# button_io.net
KiCad netlist of a schematic drawn in Altium Designer
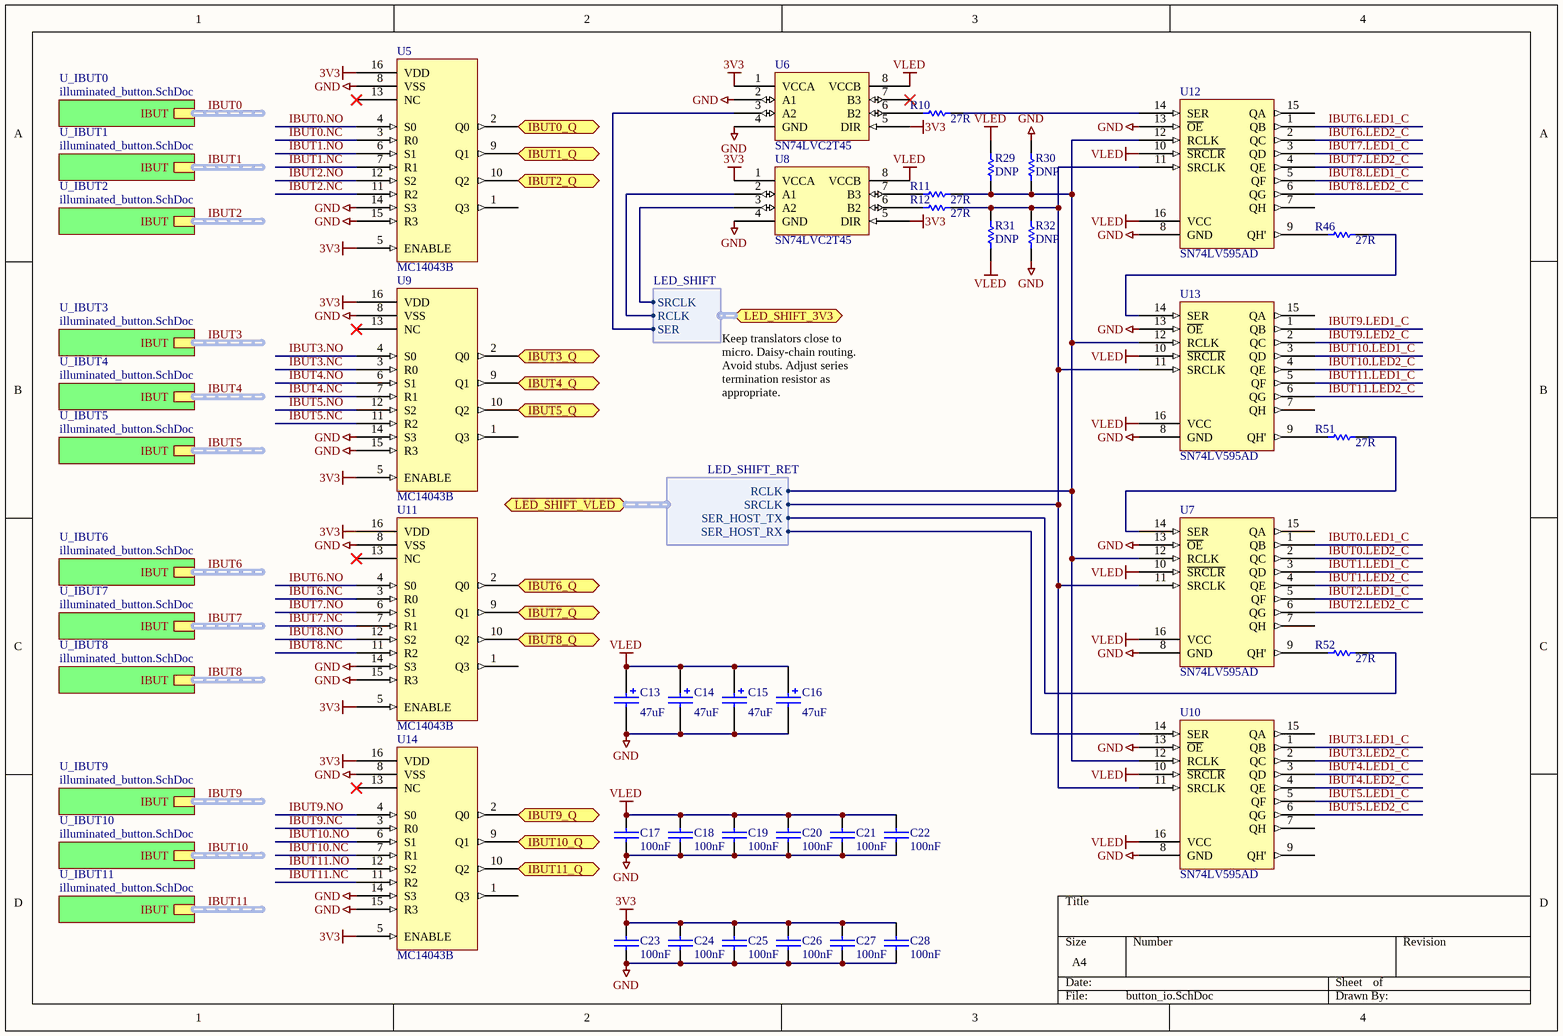
[diagram p0: button_io.SchDoc]

(export (version "E")
  (design (tool "Eeschema 10.0.6"))
  (components
    (comp (ref "C13")
      (value "47uF")
      (footprint "CAPMP7343X19N (Murata D4)")
      (description "Polarized Capacitor (Surface Mount)")
      (fields
        (field (name "MANUFACTURER") "Generic Components")
        (field (name "MANUFACTURER PART NUMBER") "ECASD40J476M025K00")
        (field (name "PUBLISHER") "Altium Limited")
      )
      (libsource (lib "RCLDQ") (part "CAP POL3"))
    )
    (comp (ref "C14")
      (value "47uF")
      (footprint "CAPMP7343X19N (Murata D4)")
      (description "Polarized Capacitor (Surface Mount)")
      (fields
        (field (name "MANUFACTURER") "Generic Components")
        (field (name "MANUFACTURER PART NUMBER") "ECASD40J476M025K00")
        (field (name "PUBLISHER") "Altium Limited")
      )
      (libsource (lib "RCLDQ") (part "CAP POL3"))
    )
    (comp (ref "C15")
      (value "47uF")
      (footprint "CAPMP7343X19N (Murata D4)")
      (description "Polarized Capacitor (Surface Mount)")
      (fields
        (field (name "MANUFACTURER") "Generic Components")
        (field (name "MANUFACTURER PART NUMBER") "ECASD40J476M025K00")
        (field (name "PUBLISHER") "Altium Limited")
      )
      (libsource (lib "RCLDQ") (part "CAP POL3"))
    )
    (comp (ref "C16")
      (value "47uF")
      (footprint "CAPMP7343X19N (Murata D4)")
      (description "Polarized Capacitor (Surface Mount)")
      (fields
        (field (name "MANUFACTURER") "Generic Components")
        (field (name "MANUFACTURER PART NUMBER") "ECASD40J476M025K00")
        (field (name "PUBLISHER") "Altium Limited")
      )
      (libsource (lib "RCLDQ") (part "CAP POL3"))
    )
    (comp (ref "C17")
      (value "100nF")
      (footprint "0603")
      (description "Capacitor")
      (fields
        (field (name "MANUFACTURER") "TDK Corporation")
        (field (name "MANUFACTURER PART NUMBER") "C1608X7R1H103K080AA")
      )
      (libsource (lib "*") (part "CAP"))
    )
    (comp (ref "C18")
      (value "100nF")
      (footprint "0603")
      (description "Capacitor")
      (fields
        (field (name "MANUFACTURER") "TDK Corporation")
        (field (name "MANUFACTURER PART NUMBER") "C1608X7R1H103K080AA")
      )
      (libsource (lib "*") (part "CAP"))
    )
    (comp (ref "C19")
      (value "100nF")
      (footprint "0603")
      (description "Capacitor")
      (fields
        (field (name "MANUFACTURER") "TDK Corporation")
        (field (name "MANUFACTURER PART NUMBER") "C1608X7R1H103K080AA")
      )
      (libsource (lib "*") (part "CAP"))
    )
    (comp (ref "C20")
      (value "100nF")
      (footprint "0603")
      (description "Capacitor")
      (fields
        (field (name "MANUFACTURER") "TDK Corporation")
        (field (name "MANUFACTURER PART NUMBER") "C1608X7R1H103K080AA")
      )
      (libsource (lib "*") (part "CAP"))
    )
    (comp (ref "C21")
      (value "100nF")
      (footprint "0603")
      (description "Capacitor")
      (fields
        (field (name "MANUFACTURER") "TDK Corporation")
        (field (name "MANUFACTURER PART NUMBER") "C1608X7R1H103K080AA")
      )
      (libsource (lib "*") (part "CAP"))
    )
    (comp (ref "C22")
      (value "100nF")
      (footprint "0603")
      (description "Capacitor")
      (fields
        (field (name "MANUFACTURER") "TDK Corporation")
        (field (name "MANUFACTURER PART NUMBER") "C1608X7R1H103K080AA")
      )
      (libsource (lib "*") (part "CAP"))
    )
    (comp (ref "C23")
      (value "100nF")
      (footprint "0603")
      (description "Capacitor")
      (fields
        (field (name "MANUFACTURER") "TDK Corporation")
        (field (name "MANUFACTURER PART NUMBER") "C1608X7R1H103K080AA")
      )
      (libsource (lib "*") (part "CAP"))
    )
    (comp (ref "C24")
      (value "100nF")
      (footprint "0603")
      (description "Capacitor")
      (fields
        (field (name "MANUFACTURER") "TDK Corporation")
        (field (name "MANUFACTURER PART NUMBER") "C1608X7R1H103K080AA")
      )
      (libsource (lib "*") (part "CAP"))
    )
    (comp (ref "C25")
      (value "100nF")
      (footprint "0603")
      (description "Capacitor")
      (fields
        (field (name "MANUFACTURER") "TDK Corporation")
        (field (name "MANUFACTURER PART NUMBER") "C1608X7R1H103K080AA")
      )
      (libsource (lib "*") (part "CAP"))
    )
    (comp (ref "C26")
      (value "100nF")
      (footprint "0603")
      (description "Capacitor")
      (fields
        (field (name "MANUFACTURER") "TDK Corporation")
        (field (name "MANUFACTURER PART NUMBER") "C1608X7R1H103K080AA")
      )
      (libsource (lib "*") (part "CAP"))
    )
    (comp (ref "C27")
      (value "100nF")
      (footprint "0603")
      (description "Capacitor")
      (fields
        (field (name "MANUFACTURER") "TDK Corporation")
        (field (name "MANUFACTURER PART NUMBER") "C1608X7R1H103K080AA")
      )
      (libsource (lib "*") (part "CAP"))
    )
    (comp (ref "C28")
      (value "100nF")
      (footprint "0603")
      (description "Capacitor")
      (fields
        (field (name "MANUFACTURER") "TDK Corporation")
        (field (name "MANUFACTURER PART NUMBER") "C1608X7R1H103K080AA")
      )
      (libsource (lib "*") (part "CAP"))
    )
    (comp (ref "R10")
      (value "27R")
      (footprint "0603")
      (description "Semiconductor Resistor")
      (fields
        (field (name "MANUFACTURER") "Panasonic Electronic Components")
        (field (name "MANUFACTURER PART NUMBER") "ERJ-3EKF27R0V")
        (field (name "PUBLISHER") "Altium Limited")
      )
      (libsource (lib "Miscellaneous Devices") (part "Res Semi"))
    )
    (comp (ref "R11")
      (value "27R")
      (footprint "0603")
      (description "Semiconductor Resistor")
      (fields
        (field (name "MANUFACTURER") "Panasonic Electronic Components")
        (field (name "MANUFACTURER PART NUMBER") "ERJ-3EKF27R0V")
        (field (name "PUBLISHER") "Altium Limited")
      )
      (libsource (lib "Miscellaneous Devices") (part "Res Semi"))
    )
    (comp (ref "R12")
      (value "27R")
      (footprint "0603")
      (description "Semiconductor Resistor")
      (fields
        (field (name "MANUFACTURER") "Panasonic Electronic Components")
        (field (name "MANUFACTURER PART NUMBER") "ERJ-3EKF27R0V")
        (field (name "PUBLISHER") "Altium Limited")
      )
      (libsource (lib "Miscellaneous Devices") (part "Res Semi"))
    )
    (comp (ref "R29")
      (value "DNP")
      (footprint "0603")
      (description "Semiconductor Resistor")
      (fields (field (name "PUBLISHER") "Altium Limited"))
      (libsource (lib "Miscellaneous Devices") (part "Res Semi"))
    )
    (comp (ref "R30")
      (value "DNP")
      (footprint "0603")
      (description "Semiconductor Resistor")
      (fields (field (name "PUBLISHER") "Altium Limited"))
      (libsource (lib "Miscellaneous Devices") (part "Res Semi"))
    )
    (comp (ref "R31")
      (value "DNP")
      (footprint "0603")
      (description "Semiconductor Resistor")
      (fields (field (name "PUBLISHER") "Altium Limited"))
      (libsource (lib "Miscellaneous Devices") (part "Res Semi"))
    )
    (comp (ref "R32")
      (value "DNP")
      (footprint "0603")
      (description "Semiconductor Resistor")
      (fields (field (name "PUBLISHER") "Altium Limited"))
      (libsource (lib "Miscellaneous Devices") (part "Res Semi"))
    )
    (comp (ref "R46")
      (value "27R")
      (footprint "0603")
      (description "Semiconductor Resistor")
      (fields
        (field (name "MANUFACTURER") "Panasonic Electronic Components")
        (field (name "MANUFACTURER PART NUMBER") "ERJ-3EKF27R0V")
        (field (name "PUBLISHER") "Altium Limited")
      )
      (libsource (lib "Miscellaneous Devices") (part "Res Semi"))
    )
    (comp (ref "R51")
      (value "27R")
      (footprint "0603")
      (description "Semiconductor Resistor")
      (fields
        (field (name "MANUFACTURER") "Panasonic Electronic Components")
        (field (name "MANUFACTURER PART NUMBER") "ERJ-3EKF27R0V")
        (field (name "PUBLISHER") "Altium Limited")
      )
      (libsource (lib "Miscellaneous Devices") (part "Res Semi"))
    )
    (comp (ref "R52")
      (value "27R")
      (footprint "0603")
      (description "Semiconductor Resistor")
      (fields
        (field (name "MANUFACTURER") "Panasonic Electronic Components")
        (field (name "MANUFACTURER PART NUMBER") "ERJ-3EKF27R0V")
        (field (name "PUBLISHER") "Altium Limited")
      )
      (libsource (lib "Miscellaneous Devices") (part "Res Semi"))
    )
    (comp (ref "U5")
      (value "MC14043B")
      (footprint "SOIC127P600X175-16N")
      (description "Quad CMOS R-S Latches")
      (fields (field (name "PART NUMBER") "MC14043BDR2G") (field (name "MANUFACTURER") "ON Semiconductor"))
      (libsource (lib "steve") (part "MC14043B"))
    )
    (comp (ref "U6")
      (value "SN74LVC2T45")
      (footprint "TSOP65P400X130-8N")
      (description "Dual-bit  Dual-supply Bus Transceiver")
      (fields (field (name "PART NUMBER") "SN74LVC2T45DCT") (field (name "MANUFACTURER") "Texas Instruments"))
      (libsource (lib "steve") (part "SN74LVC2T45"))
    )
    (comp (ref "U7")
      (value "SN74LV595AD")
      (footprint "SOIC127P600X175-16N")
      (description "8-Bit Shift Registers with 3-State Output Registers")
      (fields
        (field (name "MANUFACTURER") "Texas Instruments")
        (field (name "MANUFACTURER PART NUMBER") "SN74LV595ADR")
      )
      (libsource (lib "steve") (part "SN74LV595AD"))
    )
    (comp (ref "U8")
      (value "SN74LVC2T45")
      (footprint "TSOP65P400X130-8N")
      (description "Dual-bit  Dual-supply Bus Transceiver")
      (fields (field (name "PART NUMBER") "SN74LVC2T45DCT") (field (name "MANUFACTURER") "Texas Instruments"))
      (libsource (lib "steve") (part "SN74LVC2T45"))
    )
    (comp (ref "U9")
      (value "MC14043B")
      (footprint "SOIC127P600X175-16N")
      (description "Quad CMOS R-S Latches")
      (fields (field (name "PART NUMBER") "MC14043BDR2G") (field (name "MANUFACTURER") "ON Semiconductor"))
      (libsource (lib "steve") (part "MC14043B"))
    )
    (comp (ref "U10")
      (value "SN74LV595AD")
      (footprint "SOIC127P600X175-16N")
      (description "8-Bit Shift Registers with 3-State Output Registers")
      (fields
        (field (name "MANUFACTURER") "Texas Instruments")
        (field (name "MANUFACTURER PART NUMBER") "SN74LV595ADR")
      )
      (libsource (lib "steve") (part "SN74LV595AD"))
    )
    (comp (ref "U11")
      (value "MC14043B")
      (footprint "SOIC127P600X175-16N")
      (description "Quad CMOS R-S Latches")
      (fields (field (name "PART NUMBER") "MC14043BDR2G") (field (name "MANUFACTURER") "ON Semiconductor"))
      (libsource (lib "steve") (part "MC14043B"))
    )
    (comp (ref "U12")
      (value "SN74LV595AD")
      (footprint "SOIC127P600X175-16N")
      (description "8-Bit Shift Registers with 3-State Output Registers")
      (fields
        (field (name "MANUFACTURER") "Texas Instruments")
        (field (name "MANUFACTURER PART NUMBER") "SN74LV595ADR")
      )
      (libsource (lib "steve") (part "SN74LV595AD"))
    )
    (comp (ref "U13")
      (value "SN74LV595AD")
      (footprint "SOIC127P600X175-16N")
      (description "8-Bit Shift Registers with 3-State Output Registers")
      (fields
        (field (name "MANUFACTURER") "Texas Instruments")
        (field (name "MANUFACTURER PART NUMBER") "SN74LV595ADR")
      )
      (libsource (lib "steve") (part "SN74LV595AD"))
    )
    (comp (ref "U14")
      (value "MC14043B")
      (footprint "SOIC127P600X175-16N")
      (description "Quad CMOS R-S Latches")
      (fields (field (name "PART NUMBER") "MC14043BDR2G") (field (name "MANUFACTURER") "ON Semiconductor"))
      (libsource (lib "steve") (part "MC14043B"))
    )
  )
  (nets
    (net (code "15") (name "/IBUT0.LED1_C") (class "Default")
      (node (ref "U7") (pin "1") (pinfunction "QB_1") (pintype "output"))
    )
    (net (code "16") (name "/IBUT0.LED2_C") (class "Default")
      (node (ref "U7") (pin "2") (pinfunction "QC_2") (pintype "output"))
    )
    (net (code "17") (name "/IBUT0.NC") (class "Default")
      (node (ref "U5") (pin "3") (pinfunction "R0_3") (pintype "input"))
    )
    (net (code "18") (name "/IBUT0.NO") (class "Default")
      (node (ref "U5") (pin "4") (pinfunction "S0_4") (pintype "input"))
    )
    (net (code "19") (name "/IBUT0_Q") (class "Default")
      (node (ref "U5") (pin "2") (pinfunction "Q0_2") (pintype "output"))
    )
    (net (code "20") (name "/IBUT1.LED1_C") (class "Default")
      (node (ref "U7") (pin "3") (pinfunction "QD_3") (pintype "output"))
    )
    (net (code "21") (name "/IBUT1.LED2_C") (class "Default")
      (node (ref "U7") (pin "4") (pinfunction "QE_4") (pintype "output"))
    )
    (net (code "22") (name "/IBUT1.NC") (class "Default")
      (node (ref "U5") (pin "7") (pinfunction "R1_7") (pintype "input"))
    )
    (net (code "23") (name "/IBUT1.NO") (class "Default")
      (node (ref "U5") (pin "6") (pinfunction "S1_6") (pintype "input"))
    )
    (net (code "24") (name "/IBUT1_Q") (class "Default")
      (node (ref "U5") (pin "9") (pinfunction "Q1_9") (pintype "output"))
    )
    (net (code "25") (name "/IBUT2.LED1_C") (class "Default")
      (node (ref "U7") (pin "5") (pinfunction "QF_5") (pintype "output"))
    )
    (net (code "26") (name "/IBUT2.LED2_C") (class "Default")
      (node (ref "U7") (pin "6") (pinfunction "QG_6") (pintype "output"))
    )
    (net (code "27") (name "/IBUT2.NC") (class "Default")
      (node (ref "U5") (pin "11") (pinfunction "R2_11") (pintype "input"))
    )
    (net (code "28") (name "/IBUT2.NO") (class "Default")
      (node (ref "U5") (pin "12") (pinfunction "S2_12") (pintype "input"))
    )
    (net (code "29") (name "/IBUT2_Q") (class "Default")
      (node (ref "U5") (pin "10") (pinfunction "Q2_10") (pintype "output"))
    )
    (net (code "30") (name "/IBUT3.LED1_C") (class "Default")
      (node (ref "U10") (pin "1") (pinfunction "QB_1") (pintype "output"))
    )
    (net (code "31") (name "/IBUT3.LED2_C") (class "Default")
      (node (ref "U10") (pin "2") (pinfunction "QC_2") (pintype "output"))
    )
    (net (code "32") (name "/IBUT3.NC") (class "Default")
      (node (ref "U9") (pin "3") (pinfunction "R0_3") (pintype "input"))
    )
    (net (code "33") (name "/IBUT3.NO") (class "Default")
      (node (ref "U9") (pin "4") (pinfunction "S0_4") (pintype "input"))
    )
    (net (code "34") (name "/IBUT3_Q") (class "Default")
      (node (ref "U9") (pin "2") (pinfunction "Q0_2") (pintype "output"))
    )
    (net (code "35") (name "/IBUT4.LED1_C") (class "Default")
      (node (ref "U10") (pin "3") (pinfunction "QD_3") (pintype "output"))
    )
    (net (code "36") (name "/IBUT4.LED2_C") (class "Default")
      (node (ref "U10") (pin "4") (pinfunction "QE_4") (pintype "output"))
    )
    (net (code "37") (name "/IBUT4.NC") (class "Default")
      (node (ref "U9") (pin "7") (pinfunction "R1_7") (pintype "input"))
    )
    (net (code "38") (name "/IBUT4.NO") (class "Default")
      (node (ref "U9") (pin "6") (pinfunction "S1_6") (pintype "input"))
    )
    (net (code "39") (name "/IBUT4_Q") (class "Default")
      (node (ref "U9") (pin "9") (pinfunction "Q1_9") (pintype "output"))
    )
    (net (code "40") (name "/IBUT5.LED1_C") (class "Default")
      (node (ref "U10") (pin "5") (pinfunction "QF_5") (pintype "output"))
    )
    (net (code "41") (name "/IBUT5.LED2_C") (class "Default")
      (node (ref "U10") (pin "6") (pinfunction "QG_6") (pintype "output"))
    )
    (net (code "42") (name "/IBUT5.NC") (class "Default")
      (node (ref "U9") (pin "11") (pinfunction "R2_11") (pintype "input"))
    )
    (net (code "43") (name "/IBUT5.NO") (class "Default")
      (node (ref "U9") (pin "12") (pinfunction "S2_12") (pintype "input"))
    )
    (net (code "44") (name "/IBUT5_Q") (class "Default")
      (node (ref "U9") (pin "10") (pinfunction "Q2_10") (pintype "output"))
    )
    (net (code "45") (name "/IBUT6.LED1_C") (class "Default")
      (node (ref "U12") (pin "1") (pinfunction "QB_1") (pintype "output"))
    )
    (net (code "46") (name "/IBUT6.LED2_C") (class "Default")
      (node (ref "U12") (pin "2") (pinfunction "QC_2") (pintype "output"))
    )
    (net (code "47") (name "/IBUT6.NC") (class "Default")
      (node (ref "U11") (pin "3") (pinfunction "R0_3") (pintype "input"))
    )
    (net (code "48") (name "/IBUT6.NO") (class "Default")
      (node (ref "U11") (pin "4") (pinfunction "S0_4") (pintype "input"))
    )
    (net (code "49") (name "/IBUT6_Q") (class "Default")
      (node (ref "U11") (pin "2") (pinfunction "Q0_2") (pintype "output"))
    )
    (net (code "50") (name "/IBUT7.LED1_C") (class "Default")
      (node (ref "U12") (pin "3") (pinfunction "QD_3") (pintype "output"))
    )
    (net (code "51") (name "/IBUT7.LED2_C") (class "Default")
      (node (ref "U12") (pin "4") (pinfunction "QE_4") (pintype "output"))
    )
    (net (code "52") (name "/IBUT7.NC") (class "Default")
      (node (ref "U11") (pin "7") (pinfunction "R1_7") (pintype "input"))
    )
    (net (code "53") (name "/IBUT7.NO") (class "Default")
      (node (ref "U11") (pin "6") (pinfunction "S1_6") (pintype "input"))
    )
    (net (code "54") (name "/IBUT7_Q") (class "Default")
      (node (ref "U11") (pin "9") (pinfunction "Q1_9") (pintype "output"))
    )
    (net (code "55") (name "/IBUT8.LED1_C") (class "Default")
      (node (ref "U12") (pin "5") (pinfunction "QF_5") (pintype "output"))
    )
    (net (code "56") (name "/IBUT8.LED2_C") (class "Default")
      (node (ref "U12") (pin "6") (pinfunction "QG_6") (pintype "output"))
    )
    (net (code "57") (name "/IBUT8.NC") (class "Default")
      (node (ref "U11") (pin "11") (pinfunction "R2_11") (pintype "input"))
    )
    (net (code "58") (name "/IBUT8.NO") (class "Default")
      (node (ref "U11") (pin "12") (pinfunction "S2_12") (pintype "input"))
    )
    (net (code "59") (name "/IBUT8_Q") (class "Default")
      (node (ref "U11") (pin "10") (pinfunction "Q2_10") (pintype "output"))
    )
    (net (code "60") (name "/IBUT9.LED1_C") (class "Default")
      (node (ref "U13") (pin "1") (pinfunction "QB_1") (pintype "output"))
    )
    (net (code "61") (name "/IBUT9.LED2_C") (class "Default")
      (node (ref "U13") (pin "2") (pinfunction "QC_2") (pintype "output"))
    )
    (net (code "62") (name "/IBUT9.NC") (class "Default")
      (node (ref "U14") (pin "3") (pinfunction "R0_3") (pintype "input"))
    )
    (net (code "63") (name "/IBUT9.NO") (class "Default")
      (node (ref "U14") (pin "4") (pinfunction "S0_4") (pintype "input"))
    )
    (net (code "64") (name "/IBUT9_Q") (class "Default")
      (node (ref "U14") (pin "2") (pinfunction "Q0_2") (pintype "output"))
    )
    (net (code "65") (name "/IBUT10.LED1_C") (class "Default")
      (node (ref "U13") (pin "3") (pinfunction "QD_3") (pintype "output"))
    )
    (net (code "66") (name "/IBUT10.LED2_C") (class "Default")
      (node (ref "U13") (pin "4") (pinfunction "QE_4") (pintype "output"))
    )
    (net (code "67") (name "/IBUT10.NC") (class "Default")
      (node (ref "U14") (pin "7") (pinfunction "R1_7") (pintype "input"))
    )
    (net (code "68") (name "/IBUT10.NO") (class "Default")
      (node (ref "U14") (pin "6") (pinfunction "S1_6") (pintype "input"))
    )
    (net (code "69") (name "/IBUT10_Q") (class "Default")
      (node (ref "U14") (pin "9") (pinfunction "Q1_9") (pintype "output"))
    )
    (net (code "70") (name "/IBUT11.LED1_C") (class "Default")
      (node (ref "U13") (pin "5") (pinfunction "QF_5") (pintype "output"))
    )
    (net (code "71") (name "/IBUT11.LED2_C") (class "Default")
      (node (ref "U13") (pin "6") (pinfunction "QG_6") (pintype "output"))
    )
    (net (code "72") (name "/IBUT11.NC") (class "Default")
      (node (ref "U14") (pin "11") (pinfunction "R2_11") (pintype "input"))
    )
    (net (code "73") (name "/IBUT11.NO") (class "Default")
      (node (ref "U14") (pin "12") (pinfunction "S2_12") (pintype "input"))
    )
    (net (code "74") (name "/IBUT11_Q") (class "Default")
      (node (ref "U14") (pin "10") (pinfunction "Q2_10") (pintype "output"))
    )
    (net (code "75") (name "/SER") (class "Default")
      (node (ref "U6") (pin "3") (pinfunction "A2_3") (pintype "bidirectional"))
    )
    (net (code "76") (name "/SER_HOST_RX") (class "Default")
      (node (ref "U10") (pin "14") (pinfunction "SER_14") (pintype "input"))
    )
    (net (code "77") (name "/SER_HOST_TX") (class "Default")
      (node (ref "R52") (pin "1") (pinfunction "1_1") (pintype "passive"))
    )
    (net (code "92") (name "3V3") (class "Default")
      (node (ref "C23") (pin "1") (pinfunction "1_1") (pintype "passive"))
      (node (ref "C24") (pin "1") (pinfunction "1_1") (pintype "passive"))
      (node (ref "C25") (pin "1") (pinfunction "1_1") (pintype "passive"))
      (node (ref "C26") (pin "1") (pinfunction "1_1") (pintype "passive"))
      (node (ref "C27") (pin "1") (pinfunction "1_1") (pintype "passive"))
      (node (ref "C28") (pin "1") (pinfunction "1_1") (pintype "passive"))
      (node (ref "U11") (pin "16") (pinfunction "VDD_16") (pintype "power_in"))
      (node (ref "U11") (pin "5") (pinfunction "ENABLE_5") (pintype "input"))
      (node (ref "U14") (pin "16") (pinfunction "VDD_16") (pintype "power_in"))
      (node (ref "U14") (pin "5") (pinfunction "ENABLE_5") (pintype "input"))
      (node (ref "U5") (pin "16") (pinfunction "VDD_16") (pintype "power_in"))
      (node (ref "U5") (pin "5") (pinfunction "ENABLE_5") (pintype "input"))
      (node (ref "U6") (pin "1") (pinfunction "VCCA_1") (pintype "power_in"))
      (node (ref "U6") (pin "5") (pinfunction "DIR_5") (pintype "input"))
      (node (ref "U8") (pin "1") (pinfunction "VCCA_1") (pintype "power_in"))
      (node (ref "U8") (pin "5") (pinfunction "DIR_5") (pintype "input"))
      (node (ref "U9") (pin "16") (pinfunction "VDD_16") (pintype "power_in"))
      (node (ref "U9") (pin "5") (pinfunction "ENABLE_5") (pintype "input"))
    )
    (net (code "93") (name "GND") (class "Default")
      (node (ref "C13") (pin "2") (pinfunction "2_2") (pintype "passive"))
      (node (ref "C14") (pin "2") (pinfunction "2_2") (pintype "passive"))
      (node (ref "C15") (pin "2") (pinfunction "2_2") (pintype "passive"))
      (node (ref "C16") (pin "2") (pinfunction "2_2") (pintype "passive"))
      (node (ref "C17") (pin "2") (pinfunction "2_2") (pintype "passive"))
      (node (ref "C18") (pin "2") (pinfunction "2_2") (pintype "passive"))
      (node (ref "C19") (pin "2") (pinfunction "2_2") (pintype "passive"))
      (node (ref "C20") (pin "2") (pinfunction "2_2") (pintype "passive"))
      (node (ref "C21") (pin "2") (pinfunction "2_2") (pintype "passive"))
      (node (ref "C22") (pin "2") (pinfunction "2_2") (pintype "passive"))
      (node (ref "C23") (pin "2") (pinfunction "2_2") (pintype "passive"))
      (node (ref "C24") (pin "2") (pinfunction "2_2") (pintype "passive"))
      (node (ref "C25") (pin "2") (pinfunction "2_2") (pintype "passive"))
      (node (ref "C26") (pin "2") (pinfunction "2_2") (pintype "passive"))
      (node (ref "C27") (pin "2") (pinfunction "2_2") (pintype "passive"))
      (node (ref "C28") (pin "2") (pinfunction "2_2") (pintype "passive"))
      (node (ref "R30") (pin "1") (pinfunction "1_1") (pintype "passive"))
      (node (ref "R32") (pin "2") (pinfunction "2_2") (pintype "passive"))
      (node (ref "U10") (pin "13") (pinfunction "~{OE}_13") (pintype "input"))
      (node (ref "U10") (pin "8") (pinfunction "GND_8") (pintype "power_in"))
      (node (ref "U11") (pin "14") (pinfunction "S3_14") (pintype "input"))
      (node (ref "U11") (pin "15") (pinfunction "R3_15") (pintype "input"))
      (node (ref "U11") (pin "8") (pinfunction "VSS_8") (pintype "power_in"))
      (node (ref "U12") (pin "13") (pinfunction "~{OE}_13") (pintype "input"))
      (node (ref "U12") (pin "8") (pinfunction "GND_8") (pintype "power_in"))
      (node (ref "U13") (pin "13") (pinfunction "~{OE}_13") (pintype "input"))
      (node (ref "U13") (pin "8") (pinfunction "GND_8") (pintype "power_in"))
      (node (ref "U14") (pin "14") (pinfunction "S3_14") (pintype "input"))
      (node (ref "U14") (pin "15") (pinfunction "R3_15") (pintype "input"))
      (node (ref "U14") (pin "8") (pinfunction "VSS_8") (pintype "power_in"))
      (node (ref "U5") (pin "14") (pinfunction "S3_14") (pintype "input"))
      (node (ref "U5") (pin "15") (pinfunction "R3_15") (pintype "input"))
      (node (ref "U5") (pin "8") (pinfunction "VSS_8") (pintype "power_in"))
      (node (ref "U6") (pin "2") (pinfunction "A1_2") (pintype "bidirectional"))
      (node (ref "U6") (pin "4") (pinfunction "GND_4") (pintype "power_in"))
      (node (ref "U7") (pin "13") (pinfunction "~{OE}_13") (pintype "input"))
      (node (ref "U7") (pin "8") (pinfunction "GND_8") (pintype "power_in"))
      (node (ref "U8") (pin "4") (pinfunction "GND_4") (pintype "power_in"))
      (node (ref "U9") (pin "14") (pinfunction "S3_14") (pintype "input"))
      (node (ref "U9") (pin "15") (pinfunction "R3_15") (pintype "input"))
      (node (ref "U9") (pin "8") (pinfunction "VSS_8") (pintype "power_in"))
    )
    (net (code "94") (name "Net-(U6-B2)") (class "Default")
      (node (ref "R10") (pin "2") (pinfunction "2_2") (pintype "passive"))
      (node (ref "U6") (pin "6") (pinfunction "B2_6") (pintype "bidirectional"))
    )
    (net (code "95") (name "Net-(U7-QH')") (class "Default")
      (node (ref "R52") (pin "2") (pinfunction "2_2") (pintype "passive"))
      (node (ref "U7") (pin "9") (pinfunction "QH'_9") (pintype "output"))
    )
    (net (code "96") (name "Net-(U7-SER)") (class "Default")
      (node (ref "R51") (pin "1") (pinfunction "1_1") (pintype "passive"))
      (node (ref "U7") (pin "14") (pinfunction "SER_14") (pintype "input"))
    )
    (net (code "97") (name "Net-(U8-B2)") (class "Default")
      (node (ref "R12") (pin "2") (pinfunction "2_2") (pintype "passive"))
      (node (ref "U8") (pin "6") (pinfunction "B2_6") (pintype "bidirectional"))
    )
    (net (code "98") (name "Net-(U8-B3)") (class "Default")
      (node (ref "R11") (pin "2") (pinfunction "2_2") (pintype "passive"))
      (node (ref "U8") (pin "7") (pinfunction "B3_7") (pintype "bidirectional"))
    )
    (net (code "99") (name "Net-(U10-RCLK)") (class "Default")
      (node (ref "R11") (pin "1") (pinfunction "1_1") (pintype "passive"))
      (node (ref "R29") (pin "2") (pinfunction "2_2") (pintype "passive"))
      (node (ref "R30") (pin "2") (pinfunction "2_2") (pintype "passive"))
      (node (ref "U10") (pin "12") (pinfunction "RCLK_12") (pintype "input"))
      (node (ref "U12") (pin "12") (pinfunction "RCLK_12") (pintype "input"))
      (node (ref "U13") (pin "12") (pinfunction "RCLK_12") (pintype "input"))
      (node (ref "U7") (pin "12") (pinfunction "RCLK_12") (pintype "input"))
    )
    (net (code "100") (name "Net-(U10-SRCLK)") (class "Default")
      (node (ref "R12") (pin "1") (pinfunction "1_1") (pintype "passive"))
      (node (ref "R31") (pin "1") (pinfunction "1_1") (pintype "passive"))
      (node (ref "R32") (pin "1") (pinfunction "1_1") (pintype "passive"))
      (node (ref "U10") (pin "11") (pinfunction "SRCLK_11") (pintype "input"))
      (node (ref "U12") (pin "11") (pinfunction "SRCLK_11") (pintype "input"))
      (node (ref "U13") (pin "11") (pinfunction "SRCLK_11") (pintype "input"))
      (node (ref "U7") (pin "11") (pinfunction "SRCLK_11") (pintype "input"))
    )
    (net (code "101") (name "Net-(U12-QH')") (class "Default")
      (node (ref "R46") (pin "2") (pinfunction "2_2") (pintype "passive"))
      (node (ref "U12") (pin "9") (pinfunction "QH'_9") (pintype "output"))
    )
    (net (code "102") (name "Net-(U12-SER)") (class "Default")
      (node (ref "R10") (pin "1") (pinfunction "1_1") (pintype "passive"))
      (node (ref "U12") (pin "14") (pinfunction "SER_14") (pintype "input"))
    )
    (net (code "103") (name "Net-(U13-QH')") (class "Default")
      (node (ref "R51") (pin "2") (pinfunction "2_2") (pintype "passive"))
      (node (ref "U13") (pin "9") (pinfunction "QH'_9") (pintype "output"))
    )
    (net (code "104") (name "Net-(U13-SER)") (class "Default")
      (node (ref "R46") (pin "1") (pinfunction "1_1") (pintype "passive"))
      (node (ref "U13") (pin "14") (pinfunction "SER_14") (pintype "input"))
    )
    (net (code "105") (name "VLED") (class "Default")
      (node (ref "C13") (pin "1") (pinfunction "1_1") (pintype "passive"))
      (node (ref "C14") (pin "1") (pinfunction "1_1") (pintype "passive"))
      (node (ref "C15") (pin "1") (pinfunction "1_1") (pintype "passive"))
      (node (ref "C16") (pin "1") (pinfunction "1_1") (pintype "passive"))
      (node (ref "C17") (pin "1") (pinfunction "1_1") (pintype "passive"))
      (node (ref "C18") (pin "1") (pinfunction "1_1") (pintype "passive"))
      (node (ref "C19") (pin "1") (pinfunction "1_1") (pintype "passive"))
      (node (ref "C20") (pin "1") (pinfunction "1_1") (pintype "passive"))
      (node (ref "C21") (pin "1") (pinfunction "1_1") (pintype "passive"))
      (node (ref "C22") (pin "1") (pinfunction "1_1") (pintype "passive"))
      (node (ref "R29") (pin "1") (pinfunction "1_1") (pintype "passive"))
      (node (ref "R31") (pin "2") (pinfunction "2_2") (pintype "passive"))
      (node (ref "U10") (pin "10") (pinfunction "~{SRCLR}_10") (pintype "input"))
      (node (ref "U10") (pin "16") (pinfunction "VCC_16") (pintype "power_in"))
      (node (ref "U12") (pin "10") (pinfunction "~{SRCLR}_10") (pintype "input"))
      (node (ref "U12") (pin "16") (pinfunction "VCC_16") (pintype "power_in"))
      (node (ref "U13") (pin "10") (pinfunction "~{SRCLR}_10") (pintype "input"))
      (node (ref "U13") (pin "16") (pinfunction "VCC_16") (pintype "power_in"))
      (node (ref "U6") (pin "8") (pinfunction "VCCB_8") (pintype "power_in"))
      (node (ref "U7") (pin "10") (pinfunction "~{SRCLR}_10") (pintype "input"))
      (node (ref "U7") (pin "16") (pinfunction "VCC_16") (pintype "power_in"))
      (node (ref "U8") (pin "8") (pinfunction "VCCB_8") (pintype "power_in"))
    )
    (net (code "106") (name "unconnected-(U5-NC-Pad13)") (class "Default")
      (node (ref "U5") (pin "13") (pinfunction "NC_13") (pintype "passive+no_connect"))
    )
    (net (code "107") (name "unconnected-(U5-Q3-Pad1)") (class "Default")
      (node (ref "U5") (pin "1") (pinfunction "Q3_1") (pintype "output"))
    )
    (net (code "108") (name "unconnected-(U6-B3-Pad7)") (class "Default")
      (node (ref "U6") (pin "7") (pinfunction "B3_7") (pintype "bidirectional+no_connect"))
    )
    (net (code "109") (name "unconnected-(U7-QA-Pad15)") (class "Default")
      (node (ref "U7") (pin "15") (pinfunction "QA_15") (pintype "output"))
    )
    (net (code "110") (name "unconnected-(U7-QH-Pad7)") (class "Default")
      (node (ref "U7") (pin "7") (pinfunction "QH_7") (pintype "output"))
    )
    (net (code "111") (name "unconnected-(U8-A1-Pad2)") (class "Default")
      (node (ref "U8") (pin "2") (pinfunction "A1_2") (pintype "bidirectional"))
    )
    (net (code "112") (name "unconnected-(U8-A2-Pad3)") (class "Default")
      (node (ref "U8") (pin "3") (pinfunction "A2_3") (pintype "bidirectional"))
    )
    (net (code "113") (name "unconnected-(U9-NC-Pad13)") (class "Default")
      (node (ref "U9") (pin "13") (pinfunction "NC_13") (pintype "passive+no_connect"))
    )
    (net (code "114") (name "unconnected-(U9-Q3-Pad1)") (class "Default")
      (node (ref "U9") (pin "1") (pinfunction "Q3_1") (pintype "output"))
    )
    (net (code "115") (name "unconnected-(U10-QA-Pad15)") (class "Default")
      (node (ref "U10") (pin "15") (pinfunction "QA_15") (pintype "output"))
    )
    (net (code "116") (name "unconnected-(U10-QH'-Pad9)") (class "Default")
      (node (ref "U10") (pin "9") (pinfunction "QH'_9") (pintype "output"))
    )
    (net (code "117") (name "unconnected-(U10-QH-Pad7)") (class "Default")
      (node (ref "U10") (pin "7") (pinfunction "QH_7") (pintype "output"))
    )
    (net (code "118") (name "unconnected-(U11-NC-Pad13)") (class "Default")
      (node (ref "U11") (pin "13") (pinfunction "NC_13") (pintype "passive+no_connect"))
    )
    (net (code "119") (name "unconnected-(U11-Q3-Pad1)") (class "Default")
      (node (ref "U11") (pin "1") (pinfunction "Q3_1") (pintype "output"))
    )
    (net (code "120") (name "unconnected-(U12-QA-Pad15)") (class "Default")
      (node (ref "U12") (pin "15") (pinfunction "QA_15") (pintype "output"))
    )
    (net (code "121") (name "unconnected-(U12-QH-Pad7)") (class "Default")
      (node (ref "U12") (pin "7") (pinfunction "QH_7") (pintype "output"))
    )
    (net (code "122") (name "unconnected-(U13-QA-Pad15)") (class "Default")
      (node (ref "U13") (pin "15") (pinfunction "QA_15") (pintype "output"))
    )
    (net (code "123") (name "unconnected-(U13-QH-Pad7)") (class "Default")
      (node (ref "U13") (pin "7") (pinfunction "QH_7") (pintype "output"))
    )
    (net (code "124") (name "unconnected-(U14-NC-Pad13)") (class "Default")
      (node (ref "U14") (pin "13") (pinfunction "NC_13") (pintype "passive+no_connect"))
    )
    (net (code "125") (name "unconnected-(U14-Q3-Pad1)") (class "Default")
      (node (ref "U14") (pin "1") (pinfunction "Q3_1") (pintype "output"))
    )
  )
)
